# mote_cc3200.net
KiCad netlist of a schematic drawn in EAGLE
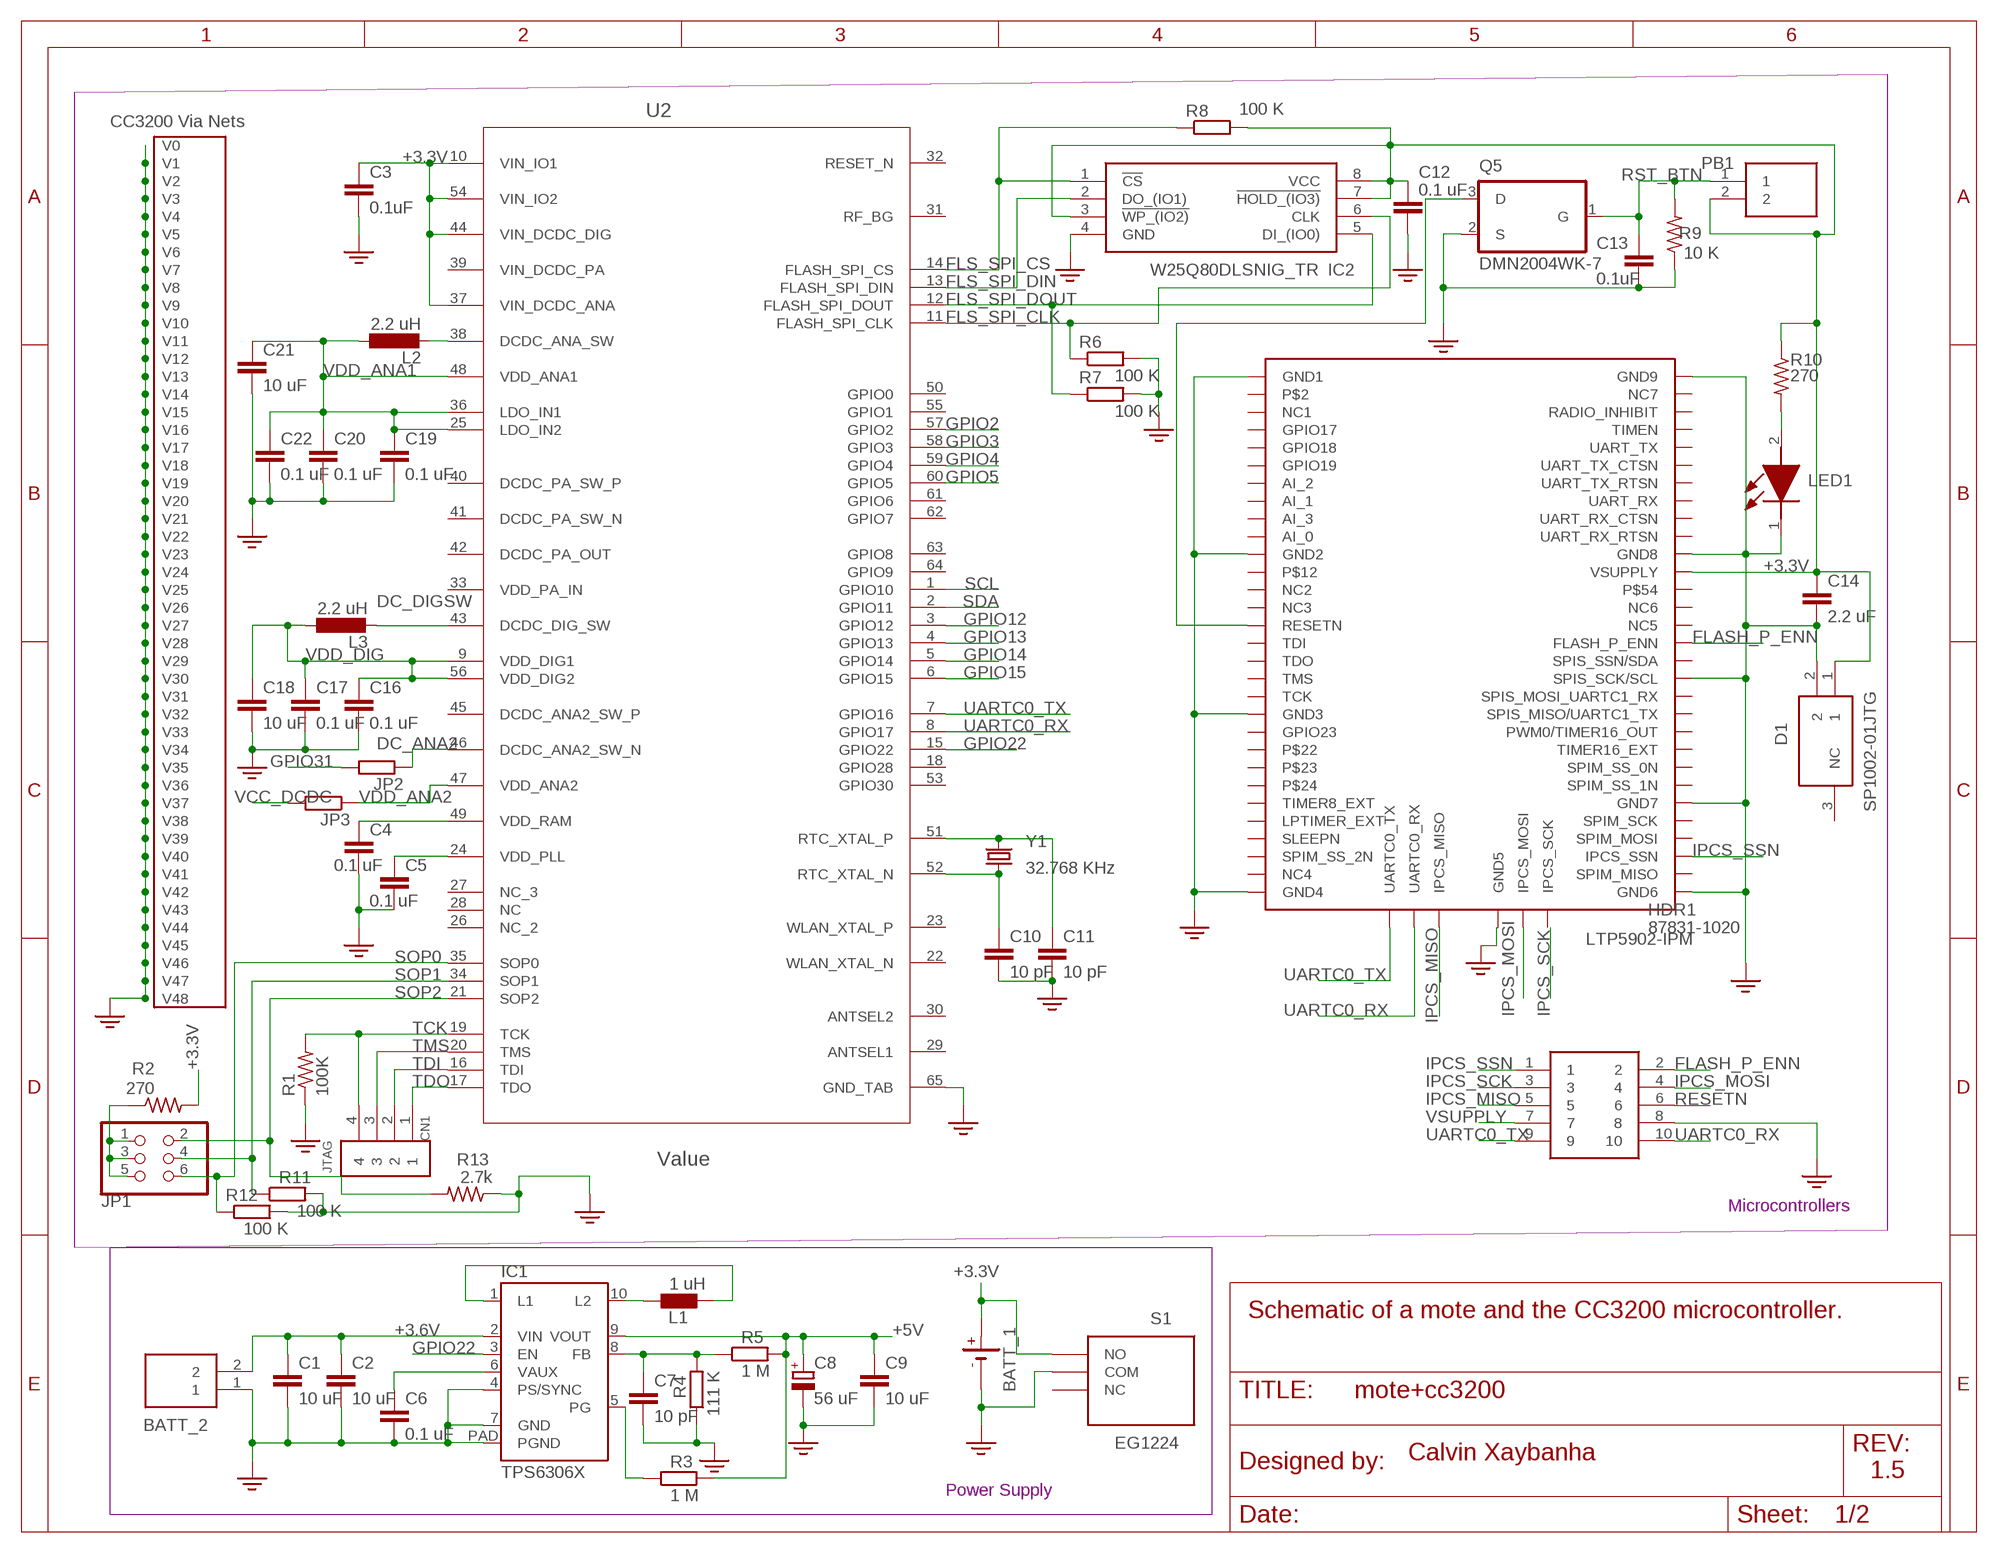
[diagram p0: schematic, sheet 1]
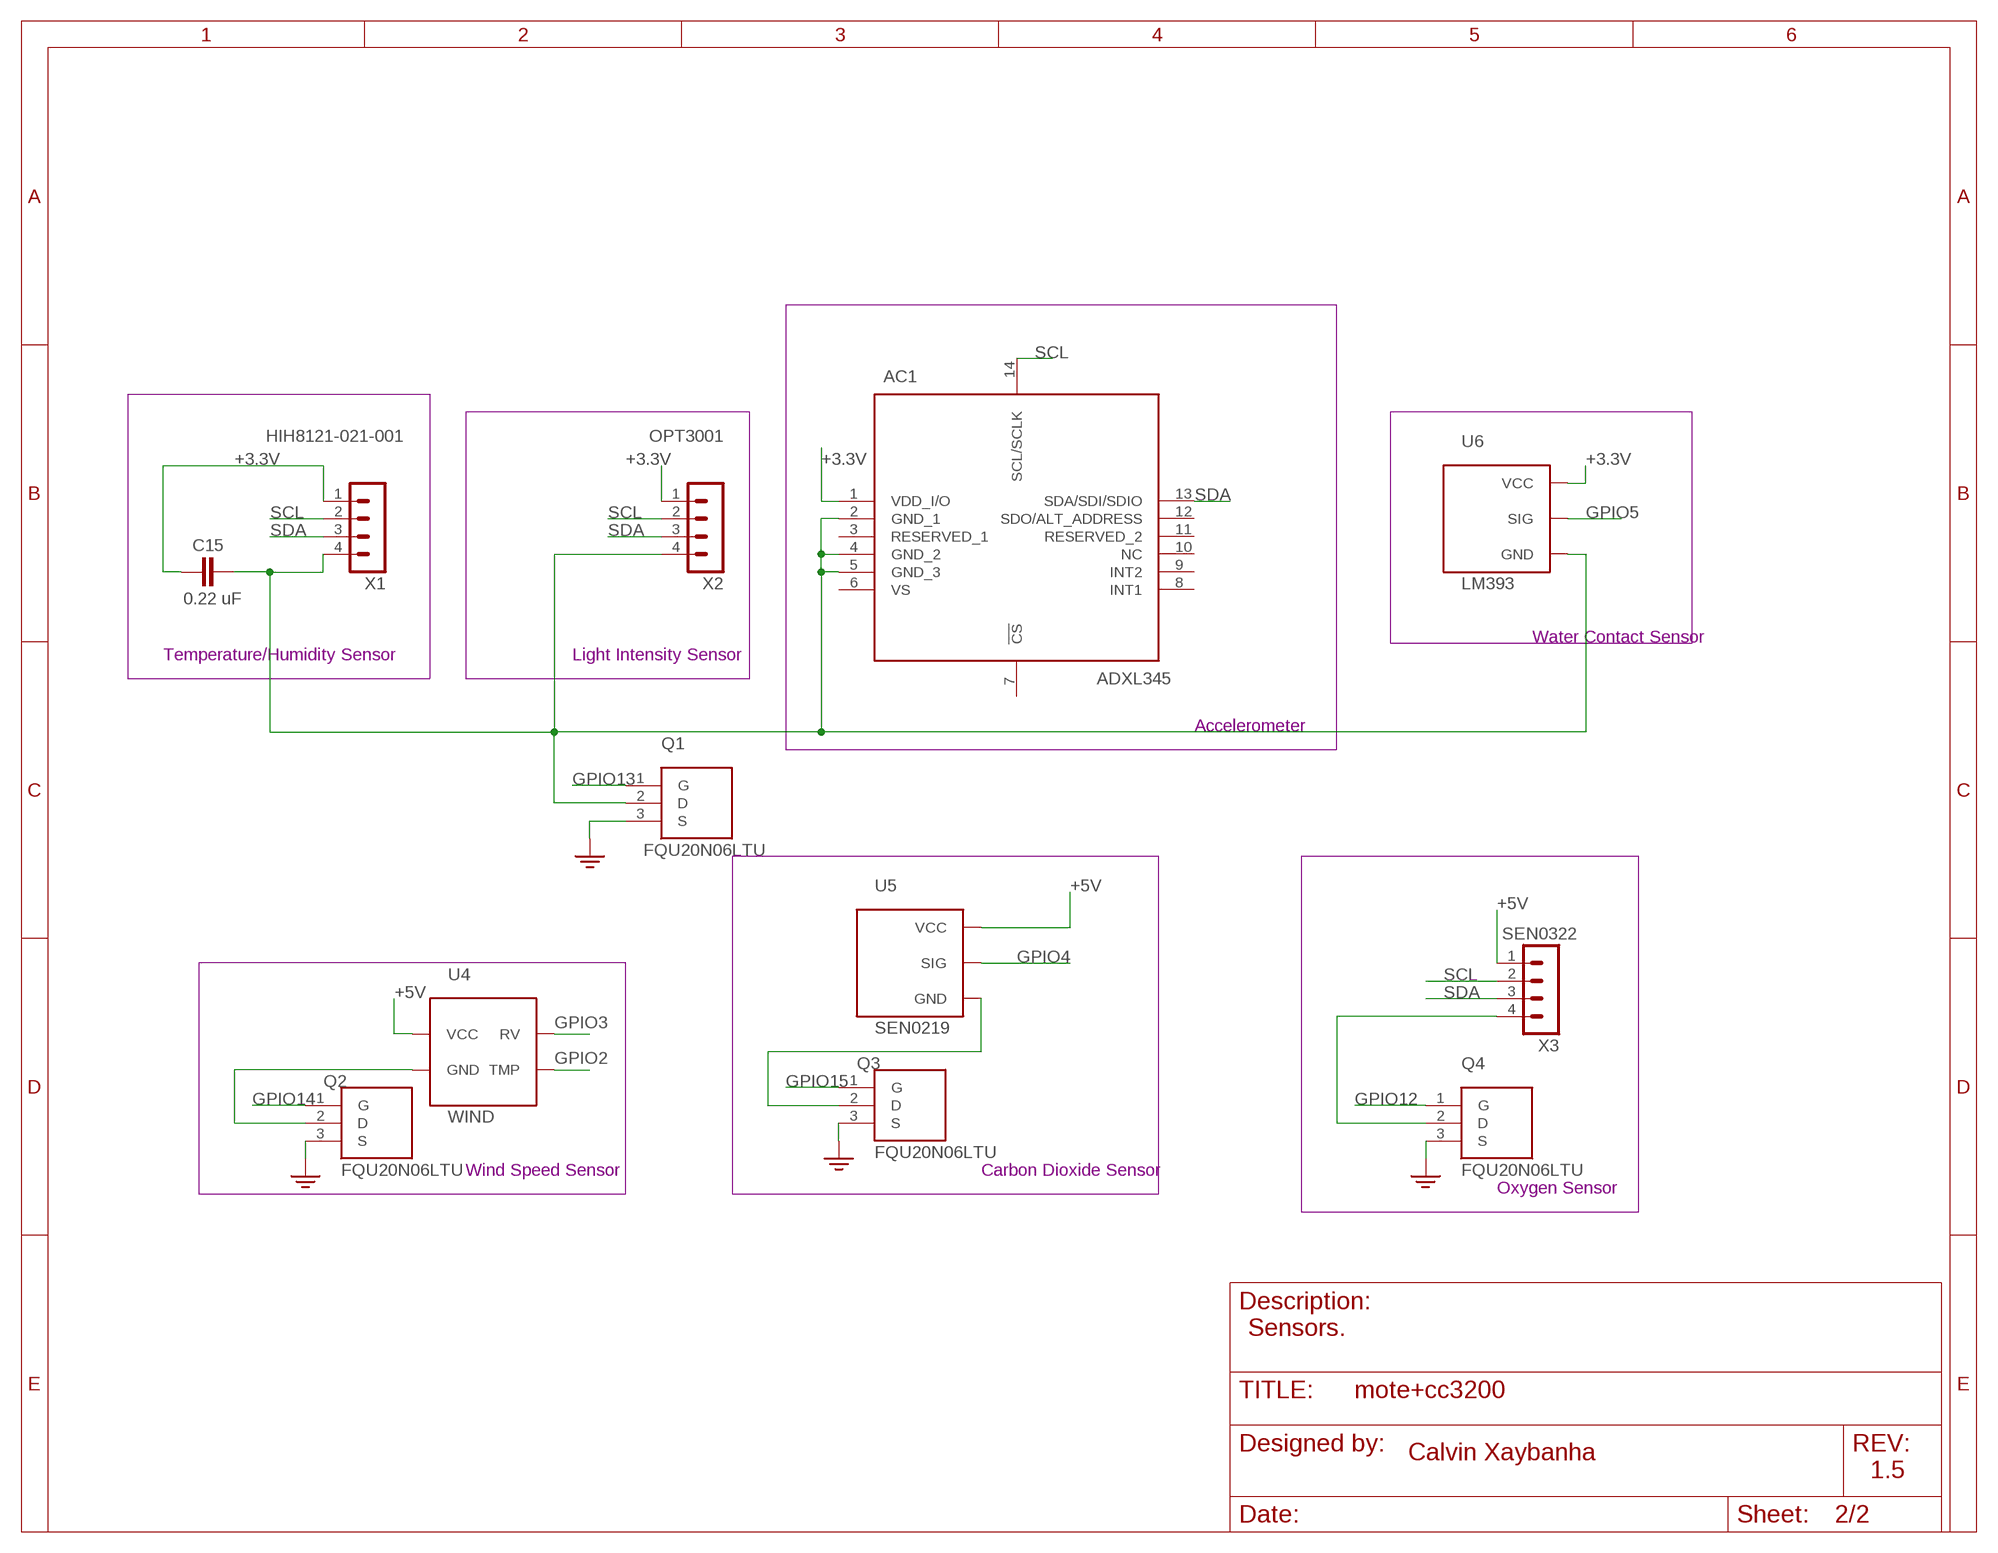
[diagram p1: schematic, sheet 2]

(export (version "E")
  (design (tool "Eeschema 10.0.6"))
  (components
    (comp (ref "BATT_1")
      (value "BATTERY_BR1225/FA")
      (footprint "eagle-import:BATTERY_BR1225_FA")
      (libsource (lib "eagle-import") (part "BATTERY_BR1225/FA"))
    )
    (comp (ref "BATT_2")
      (value "12BH23P-GR")
      (footprint "eagle-import:12BH23PGR")
      (libsource (lib "eagle-import") (part "12BH23P-GR"))
    )
    (comp (ref "C1")
      (value "10 uF")
      (footprint "eagle-import:C1808")
      (libsource (lib "eagle-import") (part "CC1808"))
    )
    (comp (ref "C2")
      (value "10 uF")
      (footprint "eagle-import:C1808")
      (libsource (lib "eagle-import") (part "CC1808"))
    )
    (comp (ref "C3")
      (value "0.1uF")
      (footprint "eagle-import:C5B3.5")
      (libsource (lib "eagle-import") (part "C5/3.5"))
    )
    (comp (ref "C4")
      (value "0.1 uF")
      (footprint "eagle-import:C1808")
      (libsource (lib "eagle-import") (part "C-EUC1808"))
    )
    (comp (ref "C5")
      (value "0.1 uF")
      (footprint "eagle-import:C1808")
      (libsource (lib "eagle-import") (part "C-EUC1808"))
    )
    (comp (ref "C6")
      (value "0.1 uF")
      (footprint "eagle-import:C1808")
      (libsource (lib "eagle-import") (part "C-EUC1808"))
    )
    (comp (ref "C7")
      (value "10 pF")
      (footprint "eagle-import:C1808")
      (libsource (lib "eagle-import") (part "CC1808"))
    )
    (comp (ref "C8")
      (value "56 uF")
      (footprint "eagle-import:E3,5-8")
      (libsource (lib "eagle-import") (part "CPOL-EUE3.5-8"))
    )
    (comp (ref "C9")
      (value "10 uF")
      (footprint "eagle-import:C1808")
      (libsource (lib "eagle-import") (part "CC1808"))
    )
    (comp (ref "C10")
      (value "10 pF")
      (footprint "eagle-import:C1808")
      (libsource (lib "eagle-import") (part "CC1808"))
    )
    (comp (ref "C11")
      (value "10 pF")
      (footprint "eagle-import:C1808")
      (libsource (lib "eagle-import") (part "CC1808"))
    )
    (comp (ref "C12")
      (value "0.1 uF")
      (footprint "eagle-import:C1808")
      (libsource (lib "eagle-import") (part "C-EUC1808"))
    )
    (comp (ref "C13")
      (value "0.1uF")
      (footprint "eagle-import:C5B3.5")
      (libsource (lib "eagle-import") (part "C5/3.5"))
    )
    (comp (ref "C14")
      (value "2.2 uF")
      (footprint "eagle-import:C1808")
      (libsource (lib "eagle-import") (part "CC1808"))
    )
    (comp (ref "C16")
      (value "0.1 uF")
      (footprint "eagle-import:C1808")
      (libsource (lib "eagle-import") (part "C-EUC1808"))
    )
    (comp (ref "C17")
      (value "0.1 uF")
      (footprint "eagle-import:C1808")
      (libsource (lib "eagle-import") (part "C-EUC1808"))
    )
    (comp (ref "C18")
      (value "10 uF")
      (footprint "eagle-import:C1808")
      (libsource (lib "eagle-import") (part "CC1808"))
    )
    (comp (ref "C19")
      (value "0.1 uF")
      (footprint "eagle-import:C1808")
      (libsource (lib "eagle-import") (part "C-EUC1808"))
    )
    (comp (ref "C20")
      (value "0.1 uF")
      (footprint "eagle-import:C1808")
      (libsource (lib "eagle-import") (part "C-EUC1808"))
    )
    (comp (ref "C21")
      (value "10 uF")
      (footprint "eagle-import:C1808")
      (libsource (lib "eagle-import") (part "CC1808"))
    )
    (comp (ref "C22")
      (value "0.1 uF")
      (footprint "eagle-import:C1808")
      (libsource (lib "eagle-import") (part "C-EUC1808"))
    )
    (comp (ref "CN1")
      (value "JTAG")
      (footprint "eagle-import:1X04-BIG")
      (libsource (lib "eagle-import") (part "1X4-BIG"))
    )
    (comp (ref "D1")
      (value "SP1002-01JTG")
      (footprint "eagle-import:SOT132P220X110-3N")
      (fields (field (name "MOUSER_PART_NUMBER") "576-SP1002-01JTG"))
      (libsource (lib "eagle-import") (part "SP1002-01JTG"))
    )
    (comp (ref "HDR1")
      (value "87831-1020")
      (footprint "eagle-import:SHDR10W55P200_2X5_1265X630X640")
      (fields (field (name "MOUSER_PART_NUMBER") "538-87831-1020"))
      (libsource (lib "eagle-import") (part "87831-1020"))
    )
    (comp (ref "IC1")
      (value "TPS6306X")
      (footprint "eagle-import:S-PWSON-N10")
      (libsource (lib "eagle-import") (part "TPS6306X"))
    )
    (comp (ref "IC2")
      (value "W25Q80DLSNIG_TR")
      (footprint "eagle-import:SOIC127P600X175-8N")
      (fields
        (field (name "MANUFACTURER_PART_NUMBER") "W25Q80DLSNIG TR")
        (field (name "MOUSER_PART_NUMBER") "454-W25Q80DLSNIGTR")
      )
      (libsource (lib "eagle-import") (part "W25Q80DLSNIG_TR"))
    )
    (comp (ref "JP1")
      (value "PINHD-2X3/90")
      (footprint "eagle-import:2X03_90")
      (libsource (lib "eagle-import") (part "PINHD-2X3/90"))
    )
    (comp (ref "JP2")
      (value "RR0201")
      (footprint "eagle-import:R0201")
      (libsource (lib "eagle-import") (part "RR0201"))
    )
    (comp (ref "JP3")
      (value "RR0201")
      (footprint "eagle-import:R0201")
      (libsource (lib "eagle-import") (part "RR0201"))
    )
    (comp (ref "L1")
      (value "1 uH")
      (footprint "eagle-import:0204_7")
      (libsource (lib "eagle-import") (part "L0204/7"))
    )
    (comp (ref "L2")
      (value "2.2 uH")
      (footprint "eagle-import:L3216C")
      (libsource (lib "eagle-import") (part "L-EUL3216C"))
    )
    (comp (ref "L3")
      (value "2.2 uH")
      (footprint "eagle-import:L3216C")
      (libsource (lib "eagle-import") (part "L-EUL3216C"))
    )
    (comp (ref "LED1")
      (value "156120RS75000")
      (footprint "eagle-import:LEDM3216X130N")
      (fields (field (name "MOUSER_PART_NUMBER") "710-156120RS75000"))
      (libsource (lib "eagle-import") (part "156120RS75000"))
    )
    (comp (ref "PB1")
      (value "FSMSM")
      (footprint "eagle-import:FSMSM")
      (fields (field (name "MOUSER_PART_NUMBER") "506-FSMSM"))
      (libsource (lib "eagle-import") (part "FSMSM"))
    )
    (comp (ref "Q5")
      (value "DMN2004WK-7")
      (footprint "eagle-import:SC70-3_DCK")
      (libsource (lib "eagle-import") (part "DMN2004WK-7"))
    )
    (comp (ref "R1")
      (value "100K")
      (footprint "eagle-import:0207_10")
      (libsource (lib "eagle-import") (part "R-US_0207/10"))
    )
    (comp (ref "R2")
      (value "270")
      (footprint "eagle-import:RES_1206")
      (fields
        (field (name "DIGIKEY_PART_NUMBER") "WSLP-.05TR-ND")
        (field (name "MANUFACTURER") "Vishay Dale")
        (field (name "MPN") "WSLP1206R0500FEA")
        (field (name "CREATED_BY") "PCBLayout.com")
      )
      (libsource (lib "eagle-import") (part "WSLP1206R0500FEA"))
    )
    (comp (ref "R3")
      (value "1 M")
      (footprint "eagle-import:R5025")
      (libsource (lib "eagle-import") (part "R-EU_R5025"))
    )
    (comp (ref "R4")
      (value "111 K")
      (footprint "eagle-import:R1206")
      (libsource (lib "eagle-import") (part "R-EU_R1206"))
    )
    (comp (ref "R5")
      (value "1 M")
      (footprint "eagle-import:R5025")
      (libsource (lib "eagle-import") (part "R-EU_R5025"))
    )
    (comp (ref "R6")
      (value "100 K")
      (footprint "eagle-import:R1206")
      (libsource (lib "eagle-import") (part "R-EU_R1206"))
    )
    (comp (ref "R7")
      (value "100 K")
      (footprint "eagle-import:R1206")
      (libsource (lib "eagle-import") (part "R-EU_R1206"))
    )
    (comp (ref "R8")
      (value "100 K")
      (footprint "eagle-import:R1206")
      (libsource (lib "eagle-import") (part "R-EU_R1206"))
    )
    (comp (ref "R9")
      (value "10 K")
      (footprint "eagle-import:RES_1206")
      (fields
        (field (name "DIGIKEY_PART_NUMBER") "WSLP-.05TR-ND")
        (field (name "MANUFACTURER") "Vishay Dale")
        (field (name "MPN") "WSLP1206R0500FEA")
        (field (name "CREATED_BY") "PCBLayout.com")
      )
      (libsource (lib "eagle-import") (part "WSLP1206R0500FEA"))
    )
    (comp (ref "R10")
      (value "270")
      (footprint "eagle-import:RES_1206")
      (fields
        (field (name "DIGIKEY_PART_NUMBER") "WSLP-.05TR-ND")
        (field (name "MANUFACTURER") "Vishay Dale")
        (field (name "MPN") "WSLP1206R0500FEA")
        (field (name "CREATED_BY") "PCBLayout.com")
      )
      (libsource (lib "eagle-import") (part "WSLP1206R0500FEA"))
    )
    (comp (ref "R11")
      (value "100 K")
      (footprint "eagle-import:R1206")
      (libsource (lib "eagle-import") (part "R-EU_R1206"))
    )
    (comp (ref "R12")
      (value "100 K")
      (footprint "eagle-import:R1206")
      (libsource (lib "eagle-import") (part "R-EU_R1206"))
    )
    (comp (ref "R13")
      (value "2.7k")
      (footprint "eagle-import:RES_1206")
      (fields
        (field (name "DIGIKEY_PART_NUMBER") "WSLP-.05TR-ND")
        (field (name "MANUFACTURER") "Vishay Dale")
        (field (name "MPN") "WSLP1206R0500FEA")
        (field (name "CREATED_BY") "PCBLayout.com")
      )
      (libsource (lib "eagle-import") (part "WSLP1206R0500FEA"))
    )
    (comp (ref "S1")
      (value "EG1224")
      (footprint "eagle-import:EG1224")
      (fields (field (name "MOUSER_PART_NUMBER") "612-EG1224"))
      (libsource (lib "eagle-import") (part "EG1224"))
    )
    (comp (ref "U2")
      (value "Value")
      (footprint "eagle-import:RGC0064A")
      (fields
        (field (name "ALTERNATEPARTNUMBER") "CC3200R1M2RGC")
        (field (name "MANUFACTURER") "Texas Instruments")
        (field (name "PARTNUMBER") "CC3200R1M2RGCR")
      )
      (libsource (lib "eagle-import") (part "CC3200R1M2RGCR"))
    )
    (comp (ref "U3")
      (value "LTP5902")
      (footprint "eagle-import:LTP5902-MMCX")
      (libsource (lib "eagle-import") (part "LTP5902"))
    )
    (comp (ref "Y1")
      (value "32.768 KHz")
      (footprint "eagle-import:7.0X5.0")
      (libsource (lib "eagle-import") (part "KX-13"))
    )
    (comp (ref "AC1")
      (value "ADXL345")
      (footprint "eagle-import:CC-14-1")
      (libsource (lib "eagle-import") (part "ADXL345"))
    )
    (comp (ref "C15")
      (value "0.22 uF")
      (footprint "eagle-import:C5B3.5")
      (libsource (lib "eagle-import") (part "C5/3.5"))
    )
    (comp (ref "Q1")
      (value "FQU20N06LTU")
      (footprint "eagle-import:TO229P250X658X985-3P")
      (fields (field (name "MOUSER_PART_NUMBER") "512-FQU20N06LTU"))
      (libsource (lib "eagle-import") (part "FQU20N06LTU"))
    )
    (comp (ref "Q2")
      (value "FQU20N06LTU")
      (footprint "eagle-import:TO229P250X658X985-3P")
      (fields (field (name "MOUSER_PART_NUMBER") "512-FQU20N06LTU"))
      (libsource (lib "eagle-import") (part "FQU20N06LTU"))
    )
    (comp (ref "Q3")
      (value "FQU20N06LTU")
      (footprint "eagle-import:TO229P250X658X985-3P")
      (fields (field (name "MOUSER_PART_NUMBER") "512-FQU20N06LTU"))
      (libsource (lib "eagle-import") (part "FQU20N06LTU"))
    )
    (comp (ref "Q4")
      (value "FQU20N06LTU")
      (footprint "eagle-import:TO229P250X658X985-3P")
      (fields (field (name "MOUSER_PART_NUMBER") "512-FQU20N06LTU"))
      (libsource (lib "eagle-import") (part "FQU20N06LTU"))
    )
    (comp (ref "U4")
      (value "WIND")
      (footprint "eagle-import:WIND")
      (libsource (lib "eagle-import") (part "WIND"))
    )
    (comp (ref "U5")
      (value "SEN0219")
      (footprint "eagle-import:SEN0219")
      (libsource (lib "eagle-import") (part "SEN0219"))
    )
    (comp (ref "U6")
      (value "LM393")
      (footprint "eagle-import:LM393")
      (libsource (lib "eagle-import") (part "LM393"))
    )
    (comp (ref "X1")
      (value "HIH8121-021-001")
      (footprint "eagle-import:B4B-PH-K-S")
      (libsource (lib "eagle-import") (part "B4B-PH-K-S"))
    )
    (comp (ref "X2")
      (value "OPT3001")
      (footprint "eagle-import:B4B-PH-K-S")
      (libsource (lib "eagle-import") (part "B4B-PH-K-S"))
    )
    (comp (ref "X3")
      (value "SEN0322")
      (footprint "eagle-import:B4B-PH-K-S")
      (libsource (lib "eagle-import") (part "B4B-PH-K-S"))
    )
  )
  (nets
    (net (code "1") (name "+3.3V") (class "Default")
      (node (ref "AC1") (pin "1") (pinfunction "VDD_I/O_1") (pintype "power_in"))
      (node (ref "BATT_1") (pin "+") (pinfunction "+_+") (pintype "passive"))
      (node (ref "C12") (pin "1") (pinfunction "1_1") (pintype "passive"))
      (node (ref "C14") (pin "1") (pinfunction "1_1") (pintype "passive"))
      (node (ref "C15") (pin "1") (pinfunction "1_1") (pintype "passive"))
      (node (ref "C3") (pin "1") (pinfunction "1_1") (pintype "passive"))
      (node (ref "D1") (pin "1") (pinfunction "1_1") (pintype "bidirectional"))
      (node (ref "IC2") (pin "3") (pinfunction "~{WP_(IO2})_3") (pintype "bidirectional"))
      (node (ref "IC2") (pin "7") (pinfunction "~{HOLD_(IO3})_7") (pintype "bidirectional"))
      (node (ref "IC2") (pin "8") (pinfunction "VCC_8") (pintype "bidirectional"))
      (node (ref "PB1") (pin "2") (pinfunction "2_2") (pintype "bidirectional"))
      (node (ref "R10") (pin "1") (pinfunction "1_1") (pintype "passive"))
      (node (ref "R2") (pin "2") (pinfunction "2_2") (pintype "passive"))
      (node (ref "R8") (pin "2") (pinfunction "2_2") (pintype "passive"))
      (node (ref "S1") (pin "1") (pinfunction "NO_1") (pintype "bidirectional"))
      (node (ref "U2") (pin "10") (pinfunction "VIN_IO1_10") (pintype "power_in"))
      (node (ref "U2") (pin "37") (pinfunction "VIN_DCDC_ANA_37") (pintype "power_in"))
      (node (ref "U2") (pin "44") (pinfunction "VIN_DCDC_DIG_44") (pintype "power_in"))
      (node (ref "U2") (pin "54") (pinfunction "VIN_IO2_54") (pintype "power_in"))
      (node (ref "U3") (pin "P55") (pinfunction "VSUPPLY_P55") (pintype "bidirectional"))
      (node (ref "U6") (pin "P$1") (pinfunction "VCC_P$1") (pintype "power_in"))
      (node (ref "X1") (pin "1") (pinfunction "1_1") (pintype "power_in"))
      (node (ref "X2") (pin "1") (pinfunction "1_1") (pintype "power_in"))
    )
    (net (code "2") (name "+3.6V") (class "Default")
      (node (ref "BATT_2") (pin "2") (pinfunction "2_2") (pintype "bidirectional"))
      (node (ref "C1") (pin "1") (pinfunction "1_1") (pintype "passive"))
      (node (ref "C2") (pin "1") (pinfunction "1_1") (pintype "passive"))
      (node (ref "IC1") (pin "2") (pinfunction "VIN_2") (pintype "passive"))
    )
    (net (code "3") (name "+5V") (class "Default")
      (node (ref "C8") (pin "+") (pinfunction "+_+") (pintype "passive"))
      (node (ref "C9") (pin "1") (pinfunction "1_1") (pintype "passive"))
      (node (ref "IC1") (pin "9") (pinfunction "VOUT_9") (pintype "passive"))
      (node (ref "R3") (pin "2") (pinfunction "2_2") (pintype "passive"))
      (node (ref "R5") (pin "2") (pinfunction "2_2") (pintype "passive"))
      (node (ref "U4") (pin "P$1") (pinfunction "VCC_P$1") (pintype "power_in"))
      (node (ref "U5") (pin "P$1") (pinfunction "VCC_P$1") (pintype "power_in"))
      (node (ref "X3") (pin "1") (pinfunction "1_1") (pintype "power_in"))
    )
    (net (code "4") (name "DCDC_PA_OUT") (class "Default")
      (node (ref "U2") (pin "42") (pinfunction "DCDC_PA_OUT_42") (pintype "power_in"))
    )
    (net (code "5") (name "DCDC_PA_SW_N") (class "Default")
      (node (ref "U2") (pin "41") (pinfunction "DCDC_PA_SW_N_41") (pintype "power_in"))
    )
    (net (code "6") (name "DCDC_PA_SW_P") (class "Default")
      (node (ref "U2") (pin "40") (pinfunction "DCDC_PA_SW_P_40") (pintype "power_in"))
    )
    (net (code "7") (name "DC_ANA2") (class "Default")
      (node (ref "JP2") (pin "1") (pinfunction "1_1") (pintype "passive"))
      (node (ref "U2") (pin "46") (pinfunction "DCDC_ANA2_SW_N_46") (pintype "bidirectional"))
    )
    (net (code "8") (name "DC_DIGSW") (class "Default")
      (node (ref "L3") (pin "2") (pinfunction "2_2") (pintype "passive"))
      (node (ref "U2") (pin "43") (pinfunction "DCDC_DIG_SW_43") (pintype "power_in"))
    )
    (net (code "9") (name "FLASH_P_ENN") (class "Default")
      (node (ref "HDR1") (pin "2") (pinfunction "2_2") (pintype "bidirectional"))
      (node (ref "U3") (pin "P51") (pinfunction "FLASH_P_ENN_P51") (pintype "bidirectional"))
    )
    (net (code "10") (name "FLS_SPI_CLK") (class "Default")
      (node (ref "IC2") (pin "6") (pinfunction "CLK_6") (pintype "bidirectional"))
      (node (ref "R6") (pin "1") (pinfunction "1_1") (pintype "passive"))
      (node (ref "U2") (pin "11") (pinfunction "FLASH_SPI_CLK_11") (pintype "output"))
    )
    (net (code "11") (name "FLS_SPI_CS") (class "Default")
      (node (ref "IC2") (pin "1") (pinfunction "~{CS}_1") (pintype "bidirectional"))
      (node (ref "R8") (pin "1") (pinfunction "1_1") (pintype "passive"))
      (node (ref "U2") (pin "14") (pinfunction "FLASH_SPI_CS_14") (pintype "output"))
    )
    (net (code "12") (name "FLS_SPI_DIN") (class "Default")
      (node (ref "IC2") (pin "2") (pinfunction "DO_(IO1)_2") (pintype "bidirectional"))
      (node (ref "U2") (pin "13") (pinfunction "FLASH_SPI_DIN_13") (pintype "input"))
    )
    (net (code "13") (name "FLS_SPI_DOUT") (class "Default")
      (node (ref "IC2") (pin "5") (pinfunction "DI_(IO0)_5") (pintype "bidirectional"))
      (node (ref "R7") (pin "1") (pinfunction "1_1") (pintype "passive"))
      (node (ref "U2") (pin "12") (pinfunction "FLASH_SPI_DOUT_12") (pintype "output"))
    )
    (net (code "14") (name "GND") (class "Default")
      (node (ref "BATT_1") (pin "-") (pinfunction "-_-") (pintype "passive"))
      (node (ref "BATT_2") (pin "1") (pinfunction "1_1") (pintype "bidirectional"))
      (node (ref "C1") (pin "2") (pinfunction "2_2") (pintype "passive"))
      (node (ref "C10") (pin "2") (pinfunction "2_2") (pintype "passive"))
      (node (ref "C11") (pin "2") (pinfunction "2_2") (pintype "passive"))
      (node (ref "C12") (pin "2") (pinfunction "2_2") (pintype "passive"))
      (node (ref "C13") (pin "1") (pinfunction "1_1") (pintype "passive"))
      (node (ref "C14") (pin "2") (pinfunction "2_2") (pintype "passive"))
      (node (ref "C16") (pin "2") (pinfunction "2_2") (pintype "passive"))
      (node (ref "C17") (pin "2") (pinfunction "2_2") (pintype "passive"))
      (node (ref "C18") (pin "2") (pinfunction "2_2") (pintype "passive"))
      (node (ref "C19") (pin "2") (pinfunction "2_2") (pintype "passive"))
      (node (ref "C2") (pin "2") (pinfunction "2_2") (pintype "passive"))
      (node (ref "C20") (pin "2") (pinfunction "2_2") (pintype "passive"))
      (node (ref "C21") (pin "2") (pinfunction "2_2") (pintype "passive"))
      (node (ref "C22") (pin "2") (pinfunction "2_2") (pintype "passive"))
      (node (ref "C3") (pin "2") (pinfunction "2_2") (pintype "passive"))
      (node (ref "C4") (pin "2") (pinfunction "2_2") (pintype "passive"))
      (node (ref "C5") (pin "2") (pinfunction "2_2") (pintype "passive"))
      (node (ref "C6") (pin "2") (pinfunction "2_2") (pintype "passive"))
      (node (ref "C7") (pin "2") (pinfunction "2_2") (pintype "passive"))
      (node (ref "C8") (pin "-") (pinfunction "-_-") (pintype "passive"))
      (node (ref "C9") (pin "2") (pinfunction "2_2") (pintype "passive"))
      (node (ref "D1") (pin "2") (pinfunction "2_2") (pintype "bidirectional"))
      (node (ref "HDR1") (pin "8") (pinfunction "8_8") (pintype "bidirectional"))
      (node (ref "IC1") (pin "4") (pinfunction "PS/SYNC_4") (pintype "passive"))
      (node (ref "IC1") (pin "7") (pinfunction "GND_7") (pintype "passive"))
      (node (ref "IC1") (pin "PAD") (pinfunction "PGND_PAD") (pintype "passive"))
      (node (ref "IC2") (pin "4") (pinfunction "GND_4") (pintype "bidirectional"))
      (node (ref "LED1") (pin "1") (pinfunction "K_1") (pintype "bidirectional"))
      (node (ref "Q1") (pin "3") (pinfunction "S_3") (pintype "bidirectional"))
      (node (ref "Q2") (pin "3") (pinfunction "S_3") (pintype "bidirectional"))
      (node (ref "Q3") (pin "3") (pinfunction "S_3") (pintype "bidirectional"))
      (node (ref "Q4") (pin "3") (pinfunction "S_3") (pintype "bidirectional"))
      (node (ref "Q5") (pin "2") (pinfunction "S_2") (pintype "bidirectional"))
      (node (ref "R1") (pin "1") (pinfunction "1_1") (pintype "passive"))
      (node (ref "R11") (pin "2") (pinfunction "2_2") (pintype "passive"))
      (node (ref "R12") (pin "2") (pinfunction "2_2") (pintype "passive"))
      (node (ref "R13") (pin "1") (pinfunction "1_1") (pintype "passive"))
      (node (ref "R4") (pin "1") (pinfunction "1_1") (pintype "passive"))
      (node (ref "R6") (pin "2") (pinfunction "2_2") (pintype "passive"))
      (node (ref "R7") (pin "2") (pinfunction "2_2") (pintype "passive"))
      (node (ref "R9") (pin "1") (pinfunction "1_1") (pintype "passive"))
      (node (ref "S1") (pin "2") (pinfunction "COM_2") (pintype "bidirectional"))
      (node (ref "U2") (pin "65") (pinfunction "GND_TAB_65") (pintype "power_in"))
      (node (ref "U2") (pin "V") (pinfunction "V0_V") (pintype "bidirectional"))
      (node (ref "U2") (pin "V_1") (pinfunction "V1_V_1") (pintype "bidirectional"))
      (node (ref "U2") (pin "V_10") (pinfunction "V10_V_10") (pintype "bidirectional"))
      (node (ref "U2") (pin "V_11") (pinfunction "V11_V_11") (pintype "bidirectional"))
      (node (ref "U2") (pin "V_12") (pinfunction "V12_V_12") (pintype "bidirectional"))
      (node (ref "U2") (pin "V_13") (pinfunction "V13_V_13") (pintype "bidirectional"))
      (node (ref "U2") (pin "V_14") (pinfunction "V14_V_14") (pintype "bidirectional"))
      (node (ref "U2") (pin "V_15") (pinfunction "V15_V_15") (pintype "bidirectional"))
      (node (ref "U2") (pin "V_16") (pinfunction "V16_V_16") (pintype "bidirectional"))
      (node (ref "U2") (pin "V_17") (pinfunction "V17_V_17") (pintype "bidirectional"))
      (node (ref "U2") (pin "V_18") (pinfunction "V18_V_18") (pintype "bidirectional"))
      (node (ref "U2") (pin "V_19") (pinfunction "V19_V_19") (pintype "bidirectional"))
      (node (ref "U2") (pin "V_2") (pinfunction "V2_V_2") (pintype "bidirectional"))
      (node (ref "U2") (pin "V_20") (pinfunction "V20_V_20") (pintype "bidirectional"))
      (node (ref "U2") (pin "V_21") (pinfunction "V21_V_21") (pintype "bidirectional"))
      (node (ref "U2") (pin "V_22") (pinfunction "V22_V_22") (pintype "bidirectional"))
      (node (ref "U2") (pin "V_23") (pinfunction "V23_V_23") (pintype "bidirectional"))
      (node (ref "U2") (pin "V_24") (pinfunction "V24_V_24") (pintype "bidirectional"))
      (node (ref "U2") (pin "V_25") (pinfunction "V25_V_25") (pintype "bidirectional"))
      (node (ref "U2") (pin "V_26") (pinfunction "V26_V_26") (pintype "bidirectional"))
      (node (ref "U2") (pin "V_27") (pinfunction "V27_V_27") (pintype "bidirectional"))
      (node (ref "U2") (pin "V_28") (pinfunction "V28_V_28") (pintype "bidirectional"))
      (node (ref "U2") (pin "V_29") (pinfunction "V29_V_29") (pintype "bidirectional"))
      (node (ref "U2") (pin "V_3") (pinfunction "V3_V_3") (pintype "bidirectional"))
      (node (ref "U2") (pin "V_30") (pinfunction "V30_V_30") (pintype "bidirectional"))
      (node (ref "U2") (pin "V_31") (pinfunction "V31_V_31") (pintype "bidirectional"))
      (node (ref "U2") (pin "V_32") (pinfunction "V32_V_32") (pintype "bidirectional"))
      (node (ref "U2") (pin "V_33") (pinfunction "V33_V_33") (pintype "bidirectional"))
      (node (ref "U2") (pin "V_34") (pinfunction "V34_V_34") (pintype "bidirectional"))
      (node (ref "U2") (pin "V_35") (pinfunction "V35_V_35") (pintype "bidirectional"))
      (node (ref "U2") (pin "V_36") (pinfunction "V36_V_36") (pintype "bidirectional"))
      (node (ref "U2") (pin "V_37") (pinfunction "V37_V_37") (pintype "bidirectional"))
      (node (ref "U2") (pin "V_38") (pinfunction "V38_V_38") (pintype "bidirectional"))
      (node (ref "U2") (pin "V_39") (pinfunction "V39_V_39") (pintype "bidirectional"))
      (node (ref "U2") (pin "V_4") (pinfunction "V4_V_4") (pintype "bidirectional"))
      (node (ref "U2") (pin "V_40") (pinfunction "V40_V_40") (pintype "bidirectional"))
      (node (ref "U2") (pin "V_41") (pinfunction "V41_V_41") (pintype "bidirectional"))
      (node (ref "U2") (pin "V_42") (pinfunction "V42_V_42") (pintype "bidirectional"))
      (node (ref "U2") (pin "V_43") (pinfunction "V43_V_43") (pintype "bidirectional"))
      (node (ref "U2") (pin "V_44") (pinfunction "V44_V_44") (pintype "bidirectional"))
      (node (ref "U2") (pin "V_45") (pinfunction "V45_V_45") (pintype "bidirectional"))
      (node (ref "U2") (pin "V_46") (pinfunction "V46_V_46") (pintype "bidirectional"))
      (node (ref "U2") (pin "V_47") (pinfunction "V47_V_47") (pintype "bidirectional"))
      (node (ref "U2") (pin "V_48") (pinfunction "V48_V_48") (pintype "bidirectional"))
      (node (ref "U2") (pin "V_5") (pinfunction "V5_V_5") (pintype "bidirectional"))
      (node (ref "U2") (pin "V_6") (pinfunction "V6_V_6") (pintype "bidirectional"))
      (node (ref "U2") (pin "V_7") (pinfunction "V7_V_7") (pintype "bidirectional"))
      (node (ref "U2") (pin "V_8") (pinfunction "V8_V_8") (pintype "bidirectional"))
      (node (ref "U2") (pin "V_9") (pinfunction "V9_V_9") (pintype "bidirectional"))
      (node (ref "U3") (pin "P1") (pinfunction "GND1_P1") (pintype "bidirectional"))
      (node (ref "U3") (pin "P11") (pinfunction "GND2_P11") (pintype "bidirectional"))
      (node (ref "U3") (pin "P20") (pinfunction "GND3_P20") (pintype "bidirectional"))
      (node (ref "U3") (pin "P30") (pinfunction "GND4_P30") (pintype "bidirectional"))
      (node (ref "U3") (pin "P34") (pinfunction "GND5_P34") (pintype "bidirectional"))
      (node (ref "U3") (pin "P37") (pinfunction "GND6_P37") (pintype "bidirectional"))
      (node (ref "U3") (pin "P42") (pinfunction "GND7_P42") (pintype "bidirectional"))
      (node (ref "U3") (pin "P49") (pinfunction "SPIS_SCK/SCL_P49") (pintype "bidirectional"))
      (node (ref "U3") (pin "P56") (pinfunction "GND8_P56") (pintype "bidirectional"))
      (node (ref "U3") (pin "P66") (pinfunction "GND9_P66") (pintype "bidirectional"))
    )
    (net (code "15") (name "GPIO2") (class "Default")
      (node (ref "U2") (pin "57") (pinfunction "GPIO2_57") (pintype "bidirectional"))
      (node (ref "U4") (pin "P$4") (pinfunction "TMP_P$4") (pintype "bidirectional"))
    )
    (net (code "16") (name "GPIO3") (class "Default")
      (node (ref "U2") (pin "58") (pinfunction "GPIO3_58") (pintype "bidirectional"))
      (node (ref "U4") (pin "P$3") (pinfunction "RV_P$3") (pintype "bidirectional"))
    )
    (net (code "17") (name "GPIO4") (class "Default")
      (node (ref "U2") (pin "59") (pinfunction "GPIO4_59") (pintype "bidirectional"))
      (node (ref "U5") (pin "P$2") (pinfunction "SIG_P$2") (pintype "bidirectional"))
    )
    (net (code "18") (name "GPIO5") (class "Default")
      (node (ref "U2") (pin "60") (pinfunction "GPIO5_60") (pintype "bidirectional"))
      (node (ref "U6") (pin "P$2") (pinfunction "SIG_P$2") (pintype "bidirectional"))
    )
    (net (code "19") (name "GPIO12") (class "Default")
      (node (ref "Q4") (pin "1") (pinfunction "G_1") (pintype "bidirectional"))
      (node (ref "U2") (pin "3") (pinfunction "GPIO12_3") (pintype "bidirectional"))
    )
    (net (code "20") (name "GPIO13") (class "Default")
      (node (ref "Q1") (pin "1") (pinfunction "G_1") (pintype "bidirectional"))
      (node (ref "U2") (pin "4") (pinfunction "GPIO13_4") (pintype "bidirectional"))
    )
    (net (code "21") (name "GPIO14") (class "Default")
      (node (ref "Q2") (pin "1") (pinfunction "G_1") (pintype "bidirectional"))
      (node (ref "U2") (pin "5") (pinfunction "GPIO14_5") (pintype "bidirectional"))
    )
    (net (code "22") (name "GPIO15") (class "Default")
      (node (ref "Q3") (pin "1") (pinfunction "G_1") (pintype "bidirectional"))
      (node (ref "U2") (pin "6") (pinfunction "GPIO15_6") (pintype "bidirectional"))
    )
    (net (code "23") (name "GPIO22") (class "Default")
      (node (ref "IC1") (pin "3") (pinfunction "EN_3") (pintype "passive"))
      (node (ref "U2") (pin "15") (pinfunction "GPIO22_15") (pintype "bidirectional"))
    )
    (net (code "24") (name "GPIO31") (class "Default")
      (node (ref "JP2") (pin "2") (pinfunction "2_2") (pintype "passive"))
    )
    (net (code "25") (name "IPCS_MISO") (class "Default")
      (node (ref "HDR1") (pin "5") (pinfunction "5_5") (pintype "bidirectional"))
      (node (ref "U3") (pin "P33") (pinfunction "IPCS_MISO_P33") (pintype "bidirectional"))
    )
    (net (code "26") (name "IPCS_MOSI") (class "Default")
      (node (ref "U3") (pin "P35") (pinfunction "IPCS_MOSI_P35") (pintype "bidirectional"))
    )
    (net (code "27") (name "IPCS_SCK") (class "Default")
      (node (ref "HDR1") (pin "3") (pinfunction "3_3") (pintype "bidirectional"))
    )
    (net (code "28") (name "IPCS_SSN") (class "Default")
      (node (ref "HDR1") (pin "1") (pinfunction "1_1") (pintype "bidirectional"))
      (node (ref "U3") (pin "P39") (pinfunction "IPCS_SSN_P39") (pintype "bidirectional"))
    )
    (net (code "29") (name "Net-(AC1-GND_1)") (class "Default")
      (node (ref "AC1") (pin "2") (pinfunction "GND_1_2") (pintype "power_in"))
      (node (ref "AC1") (pin "4") (pinfunction "GND_2_4") (pintype "power_in"))
      (node (ref "AC1") (pin "5") (pinfunction "GND_3_5") (pintype "power_in"))
      (node (ref "C15") (pin "2") (pinfunction "2_2") (pintype "passive"))
      (node (ref "Q1") (pin "2") (pinfunction "D_2") (pintype "bidirectional"))
      (node (ref "U6") (pin "P$3") (pinfunction "GND_P$3") (pintype "power_in"))
      (node (ref "X1") (pin "4") (pinfunction "4_4") (pintype "bidirectional"))
      (node (ref "X2") (pin "4") (pinfunction "4_4") (pintype "bidirectional"))
    )
    (net (code "30") (name "Net-(IC1-FB)") (class "Default")
      (node (ref "C7") (pin "1") (pinfunction "1_1") (pintype "passive"))
      (node (ref "IC1") (pin "8") (pinfunction "FB_8") (pintype "passive"))
      (node (ref "R4") (pin "2") (pinfunction "2_2") (pintype "passive"))
      (node (ref "R5") (pin "1") (pinfunction "1_1") (pintype "passive"))
    )
    (net (code "31") (name "Net-(IC1-L1)") (class "Default")
      (node (ref "IC1") (pin "1") (pinfunction "L1_1") (pintype "passive"))
      (node (ref "L1") (pin "2") (pinfunction "2_2") (pintype "passive"))
    )
    (net (code "32") (name "Net-(IC1-L2)") (class "Default")
      (node (ref "IC1") (pin "10") (pinfunction "L2_10") (pintype "passive"))
      (node (ref "L1") (pin "1") (pinfunction "1_1") (pintype "passive"))
    )
    (net (code "33") (name "Net-(IC1-PG)") (class "Default")
      (node (ref "IC1") (pin "5") (pinfunction "PG_5") (pintype "passive"))
      (node (ref "R3") (pin "1") (pinfunction "1_1") (pintype "passive"))
    )
    (net (code "34") (name "Net-(IC1-VAUX)") (class "Default")
      (node (ref "C6") (pin "1") (pinfunction "1_1") (pintype "passive"))
      (node (ref "IC1") (pin "6") (pinfunction "VAUX_6") (pintype "passive"))
    )
    (net (code "35") (name "Net-(JP1-Pad1)") (class "Default")
      (node (ref "JP1") (pin "1") (pinfunction "1_1") (pintype "passive"))
      (node (ref "JP1") (pin "3") (pinfunction "3_3") (pintype "passive"))
      (node (ref "JP1") (pin "5") (pinfunction "5_5") (pintype "passive"))
      (node (ref "R2") (pin "1") (pinfunction "1_1") (pintype "passive"))
    )
    (net (code "36") (name "Net-(LED1-A)") (class "Default")
      (node (ref "LED1") (pin "2") (pinfunction "A_2") (pintype "bidirectional"))
      (node (ref "R10") (pin "2") (pinfunction "2_2") (pintype "passive"))
    )
    (net (code "37") (name "Net-(Q2-D)") (class "Default")
      (node (ref "Q2") (pin "2") (pinfunction "D_2") (pintype "bidirectional"))
      (node (ref "U4") (pin "P$2") (pinfunction "GND_P$2") (pintype "power_in"))
    )
    (net (code "38") (name "Net-(Q3-D)") (class "Default")
      (node (ref "Q3") (pin "2") (pinfunction "D_2") (pintype "bidirectional"))
      (node (ref "U5") (pin "P$3") (pinfunction "GND_P$3") (pintype "power_in"))
    )
    (net (code "39") (name "Net-(Q4-D)") (class "Default")
      (node (ref "Q4") (pin "2") (pinfunction "D_2") (pintype "bidirectional"))
      (node (ref "X3") (pin "4") (pinfunction "4_4") (pintype "bidirectional"))
    )
    (net (code "40") (name "Net-(U2-DCDC_ANA_SW)") (class "Default")
      (node (ref "L2") (pin "2") (pinfunction "2_2") (pintype "passive"))
      (node (ref "U2") (pin "38") (pinfunction "DCDC_ANA_SW_38") (pintype "power_in"))
    )
    (net (code "41") (name "Net-(U2-RTC_XTAL_N)") (class "Default")
      (node (ref "C10") (pin "1") (pinfunction "1_1") (pintype "passive"))
      (node (ref "U2") (pin "52") (pinfunction "RTC_XTAL_N_52") (pintype "passive"))
      (node (ref "Y1") (pin "1") (pinfunction "1_1") (pintype "passive"))
    )
    (net (code "42") (name "Net-(U2-RTC_XTAL_P)") (class "Default")
      (node (ref "C11") (pin "1") (pinfunction "1_1") (pintype "passive"))
      (node (ref "U2") (pin "51") (pinfunction "RTC_XTAL_P_51") (pintype "passive"))
      (node (ref "Y1") (pin "3") (pinfunction "2_3") (pintype "passive"))
    )
    (net (code "43") (name "Net-(U2-VDD_PLL)") (class "Default")
      (node (ref "C5") (pin "1") (pinfunction "1_1") (pintype "passive"))
      (node (ref "U2") (pin "24") (pinfunction "VDD_PLL_24") (pintype "power_in"))
    )
    (net (code "44") (name "Net-(U2-VDD_RAM)") (class "Default")
      (node (ref "C4") (pin "1") (pinfunction "1_1") (pintype "passive"))
      (node (ref "U2") (pin "49") (pinfunction "VDD_RAM_49") (pintype "power_in"))
    )
    (net (code "45") (name "RESETN") (class "Default")
      (node (ref "HDR1") (pin "6") (pinfunction "6_6") (pintype "bidirectional"))
      (node (ref "Q5") (pin "3") (pinfunction "D_3") (pintype "bidirectional"))
      (node (ref "U3") (pin "P15") (pinfunction "RESETN_P15") (pintype "bidirectional"))
    )
    (net (code "46") (name "RST_BTN") (class "Default")
      (node (ref "C13") (pin "2") (pinfunction "2_2") (pintype "passive"))
      (node (ref "PB1") (pin "1") (pinfunction "1_1") (pintype "bidirectional"))
      (node (ref "Q5") (pin "1") (pinfunction "G_1") (pintype "bidirectional"))
      (node (ref "R9") (pin "2") (pinfunction "2_2") (pintype "passive"))
    )
    (net (code "47") (name "SCL") (class "Default")
      (node (ref "AC1") (pin "14") (pinfunction "SCL/SCLK_14") (pintype "input"))
      (node (ref "U2") (pin "1") (pinfunction "GPIO10_1") (pintype "bidirectional"))
      (node (ref "X1") (pin "2") (pinfunction "2_2") (pintype "power_in"))
      (node (ref "X2") (pin "2") (pinfunction "2_2") (pintype "power_in"))
      (node (ref "X3") (pin "2") (pinfunction "2_2") (pintype "power_in"))
    )
    (net (code "48") (name "SDA") (class "Default")
      (node (ref "AC1") (pin "13") (pinfunction "SDA/SDI/SDIO_13") (pintype "bidirectional"))
      (node (ref "U2") (pin "2") (pinfunction "GPIO11_2") (pintype "bidirectional"))
      (node (ref "X1") (pin "3") (pinfunction "3_3") (pintype "bidirectional"))
      (node (ref "X2") (pin "3") (pinfunction "3_3") (pintype "bidirectional"))
      (node (ref "X3") (pin "3") (pinfunction "3_3") (pintype "bidirectional"))
    )
    (net (code "49") (name "SOP0") (class "Default")
      (node (ref "JP1") (pin "6") (pinfunction "6_6") (pintype "passive"))
      (node (ref "R12") (pin "1") (pinfunction "1_1") (pintype "passive"))
      (node (ref "U2") (pin "35") (pinfunction "SOP0_35") (pintype "input"))
    )
    (net (code "50") (name "SOP1") (class "Default")
      (node (ref "JP1") (pin "4") (pinfunction "4_4") (pintype "passive"))
      (node (ref "R11") (pin "1") (pinfunction "1_1") (pintype "passive"))
      (node (ref "U2") (pin "34") (pinfunction "SOP1_34") (pintype "input"))
    )
    (net (code "51") (name "SOP2") (class "Default")
      (node (ref "JP1") (pin "2") (pinfunction "2_2") (pintype "passive"))
      (node (ref "R13") (pin "2") (pinfunction "2_2") (pintype "passive"))
      (node (ref "U2") (pin "21") (pinfunction "SOP2_21") (pintype "output"))
    )
    (net (code "52") (name "TCK") (class "Default")
      (node (ref "CN1") (pin "4") (pinfunction "4_4") (pintype "bidirectional"))
      (node (ref "R1") (pin "2") (pinfunction "2_2") (pintype "passive"))
      (node (ref "U2") (pin "19") (pinfunction "TCK_19") (pintype "bidirectional"))
    )
    (net (code "53") (name "TDI") (class "Default")
      (node (ref "CN1") (pin "2") (pinfunction "2_2") (pintype "bidirectional"))
      (node (ref "U2") (pin "16") (pinfunction "TDI_16") (pintype "bidirectional"))
    )
    (net (code "54") (name "TDO") (class "Default")
      (node (ref "CN1") (pin "1") (pinfunction "1_1") (pintype "bidirectional"))
      (node (ref "U2") (pin "17") (pinfunction "TDO_17") (pintype "bidirectional"))
    )
    (net (code "55") (name "TMS") (class "Default")
      (node (ref "CN1") (pin "3") (pinfunction "3_3") (pintype "bidirectional"))
      (node (ref "U2") (pin "20") (pinfunction "TMS_20") (pintype "bidirectional"))
    )
    (net (code "56") (name "UARTC0_RX") (class "Default")
      (node (ref "HDR1") (pin "10") (pinfunction "10_10") (pintype "bidirectional"))
      (node (ref "U2") (pin "8") (pinfunction "GPIO17_8") (pintype "bidirectional"))
      (node (ref "U3") (pin "P32") (pinfunction "UARTC0_RX_P32") (pintype "bidirectional"))
    )
    (net (code "57") (name "UARTC0_TX") (class "Default")
      (node (ref "HDR1") (pin "9") (pinfunction "9_9") (pintype "bidirectional"))
      (node (ref "U2") (pin "7") (pinfunction "GPIO16_7") (pintype "bidirectional"))
      (node (ref "U3") (pin "P31") (pinfunction "UARTC0_TX_P31") (pintype "bidirectional"))
    )
    (net (code "58") (name "VCC_DCDC") (class "Default")
      (node (ref "JP3") (pin "2") (pinfunction "2_2") (pintype "passive"))
    )
    (net (code "59") (name "VDD_ANA1") (class "Default")
      (node (ref "C19") (pin "1") (pinfunction "1_1") (pintype "passive"))
      (node (ref "C20") (pin "1") (pinfunction "1_1") (pintype "passive"))
      (node (ref "C21") (pin "1") (pinfunction "1_1") (pintype "passive"))
      (node (ref "C22") (pin "1") (pinfunction "1_1") (pintype "passive"))
      (node (ref "L2") (pin "1") (pinfunction "1_1") (pintype "passive"))
      (node (ref "U2") (pin "25") (pinfunction "LDO_IN2_25") (pintype "power_in"))
      (node (ref "U2") (pin "36") (pinfunction "LDO_IN1_36") (pintype "power_in"))
      (node (ref "U2") (pin "48") (pinfunction "VDD_ANA1_48") (pintype "power_in"))
    )
    (net (code "60") (name "VDD_ANA2") (class "Default")
      (node (ref "JP3") (pin "1") (pinfunction "1_1") (pintype "passive"))
      (node (ref "U2") (pin "47") (pinfunction "VDD_ANA2_47") (pintype "power_in"))
    )
    (net (code "61") (name "VDD_DIG") (class "Default")
      (node (ref "C16") (pin "1") (pinfunction "1_1") (pintype "passive"))
      (node (ref "C17") (pin "1") (pinfunction "1_1") (pintype "passive"))
      (node (ref "C18") (pin "1") (pinfunction "1_1") (pintype "passive"))
      (node (ref "L3") (pin "1") (pinfunction "1_1") (pintype "passive"))
      (node (ref "U2") (pin "56") (pinfunction "VDD_DIG2_56") (pintype "power_in"))
      (node (ref "U2") (pin "9") (pinfunction "VDD_DIG1_9") (pintype "power_in"))
    )
    (net (code "62") (name "VDD_PA_IN") (class "Default")
      (node (ref "U2") (pin "33") (pinfunction "VDD_PA_IN_33") (pintype "power_in"))
    )
    (net (code "63") (name "VIN_DCDC_PA") (class "Default")
      (node (ref "U2") (pin "39") (pinfunction "VIN_DCDC_PA_39") (pintype "power_in"))
    )
    (net (code "64") (name "VSUPPLY") (class "Default")
      (node (ref "HDR1") (pin "7") (pinfunction "7_7") (pintype "bidirectional"))
    )
    (net (code "65") (name "unconnected-(AC1-INT1-Pad8)") (class "Default")
      (node (ref "AC1") (pin "8") (pinfunction "INT1_8") (pintype "input"))
    )
    (net (code "66") (name "unconnected-(AC1-INT2-Pad9)") (class "Default")
      (node (ref "AC1") (pin "9") (pinfunction "INT2_9") (pintype "input"))
    )
    (net (code "67") (name "unconnected-(AC1-NC-Pad10)") (class "Default")
      (node (ref "AC1") (pin "10") (pinfunction "NC_10") (pintype "no_connect"))
    )
    (net (code "68") (name "unconnected-(AC1-RESERVED_1-Pad3)") (class "Default")
      (node (ref "AC1") (pin "3") (pinfunction "RESERVED_1_3") (pintype "bidirectional"))
    )
    (net (code "69") (name "unconnected-(AC1-RESERVED_2-Pad11)") (class "Default")
      (node (ref "AC1") (pin "11") (pinfunction "RESERVED_2_11") (pintype "bidirectional"))
    )
    (net (code "70") (name "unconnected-(AC1-SDO{slash}ALT_ADDRESS-Pad12)") (class "Default")
      (node (ref "AC1") (pin "12") (pinfunction "SDO/ALT_ADDRESS_12") (pintype "bidirectional"))
    )
    (net (code "71") (name "unconnected-(AC1-VS-Pad6)") (class "Default")
      (node (ref "AC1") (pin "6") (pinfunction "VS_6") (pintype "bidirectional"))
    )
    (net (code "72") (name "unconnected-(AC1-~{CS}-Pad7)") (class "Default")
      (node (ref "AC1") (pin "7") (pinfunction "~{CS}_7") (pintype "input"))
    )
    (net (code "73") (name "unconnected-(D1-NC-Pad3)") (class "Default")
      (node (ref "D1") (pin "3") (pinfunction "NC_3") (pintype "no_connect"))
    )
    (net (code "74") (name "unconnected-(HDR1-Pad4)") (class "Default")
      (node (ref "HDR1") (pin "4") (pinfunction "4_4") (pintype "bidirectional"))
    )
    (net (code "75") (name "unconnected-(S1-NC-Pad3)") (class "Default")
      (node (ref "S1") (pin "3") (pinfunction "NC_3") (pintype "no_connect"))
    )
    (net (code "76") (name "unconnected-(S1-PadMH1)") (class "Default")
      (node (ref "S1") (pin "MH1") (pinfunction "MH1_MH1") (pintype "bidirectional"))
    )
    (net (code "77") (name "unconnected-(S1-PadMH2)") (class "Default")
      (node (ref "S1") (pin "MH2") (pinfunction "MH2_MH2") (pintype "bidirectional"))
    )
    (net (code "78") (name "unconnected-(S1-PadMH3)") (class "Default")
      (node (ref "S1") (pin "MH3") (pinfunction "MH3_MH3") (pintype "bidirectional"))
    )
    (net (code "79") (name "unconnected-(S1-PadMH4)") (class "Default")
      (node (ref "S1") (pin "MH4") (pinfunction "MH4_MH4") (pintype "bidirectional"))
    )
    (net (code "80") (name "unconnected-(U2-ANTSEL1-Pad29)") (class "Default")
      (node (ref "U2") (pin "29") (pinfunction "ANTSEL1_29") (pintype "output"))
    )
    (net (code "81") (name "unconnected-(U2-ANTSEL2-Pad30)") (class "Default")
      (node (ref "U2") (pin "30") (pinfunction "ANTSEL2_30") (pintype "output"))
    )
    (net (code "82") (name "unconnected-(U2-DCDC_ANA2_SW_P-Pad45)") (class "Default")
      (node (ref "U2") (pin "45") (pinfunction "DCDC_ANA2_SW_P_45") (pintype "bidirectional"))
    )
    (net (code "83") (name "unconnected-(U2-GPIO0-Pad50)") (class "Default")
      (node (ref "U2") (pin "50") (pinfunction "GPIO0_50") (pintype "bidirectional"))
    )
    (net (code "84") (name "unconnected-(U2-GPIO1-Pad55)") (class "Default")
      (node (ref "U2") (pin "55") (pinfunction "GPIO1_55") (pintype "bidirectional"))
    )
    (net (code "85") (name "unconnected-(U2-GPIO6-Pad61)") (class "Default")
      (node (ref "U2") (pin "61") (pinfunction "GPIO6_61") (pintype "bidirectional"))
    )
    (net (code "86") (name "unconnected-(U2-GPIO7-Pad62)") (class "Default")
      (node (ref "U2") (pin "62") (pinfunction "GPIO7_62") (pintype "bidirectional"))
    )
    (net (code "87") (name "unconnected-(U2-GPIO8-Pad63)") (class "Default")
      (node (ref "U2") (pin "63") (pinfunction "GPIO8_63") (pintype "bidirectional"))
    )
    (net (code "88") (name "unconnected-(U2-GPIO9-Pad64)") (class "Default")
      (node (ref "U2") (pin "64") (pinfunction "GPIO9_64") (pintype "bidirectional"))
    )
    (net (code "89") (name "unconnected-(U2-GPIO28-Pad18)") (class "Default")
      (node (ref "U2") (pin "18") (pinfunction "GPIO28_18") (pintype "bidirectional"))
    )
    (net (code "90") (name "unconnected-(U2-GPIO30-Pad53)") (class "Default")
      (node (ref "U2") (pin "53") (pinfunction "GPIO30_53") (pintype "bidirectional"))
    )
    (net (code "91") (name "unconnected-(U2-NC-Pad28)") (class "Default")
      (node (ref "U2") (pin "28") (pinfunction "NC_28") (pintype "passive"))
    )
    (net (code "92") (name "unconnected-(U2-NC_2-Pad26)") (class "Default")
      (node (ref "U2") (pin "26") (pinfunction "NC_2_26") (pintype "passive"))
    )
    (net (code "93") (name "unconnected-(U2-NC_3-Pad27)") (class "Default")
      (node (ref "U2") (pin "27") (pinfunction "NC_3_27") (pintype "passive"))
    )
    (net (code "94") (name "unconnected-(U2-RESET_N-Pad32)") (class "Default")
      (node (ref "U2") (pin "32") (pinfunction "RESET_N_32") (pintype "input"))
    )
    (net (code "95") (name "unconnected-(U2-RF_BG-Pad31)") (class "Default")
      (node (ref "U2") (pin "31") (pinfunction "RF_BG_31") (pintype "passive"))
    )
    (net (code "96") (name "unconnected-(U2-WLAN_XTAL_N-Pad22)") (class "Default")
      (node (ref "U2") (pin "22") (pinfunction "WLAN_XTAL_N_22") (pintype "passive"))
    )
    (net (code "97") (name "unconnected-(U2-WLAN_XTAL_P-Pad23)") (class "Default")
      (node (ref "U2") (pin "23") (pinfunction "WLAN_XTAL_P_23") (pintype "passive"))
    )
    (net (code "98") (name "unconnected-(U3-AI_0-PadP10)") (class "Default")
      (node (ref "U3") (pin "P10") (pinfunction "AI_0_P10") (pintype "bidirectional"))
    )
    (net (code "99") (name "unconnected-(U3-AI_1-PadP8)") (class "Default")
      (node (ref "U3") (pin "P8") (pinfunction "AI_1_P8") (pintype "bidirectional"))
    )
    (net (code "100") (name "unconnected-(U3-AI_2-PadP7)") (class "Default")
      (node (ref "U3") (pin "P7") (pinfunction "AI_2_P7") (pintype "bidirectional"))
    )
    (net (code "101") (name "unconnected-(U3-AI_3-PadP9)") (class "Default")
      (node (ref "U3") (pin "P9") (pinfunction "AI_3_P9") (pintype "bidirectional"))
    )
    (net (code "102") (name "unconnected-(U3-GPIO17-PadP4)") (class "Default")
      (node (ref "U3") (pin "P4") (pinfunction "GPIO17_P4") (pintype "bidirectional"))
    )
    (net (code "103") (name "unconnected-(U3-GPIO18-PadP5)") (class "Default")
      (node (ref "U3") (pin "P5") (pinfunction "GPIO18_P5") (pintype "bidirectional"))
    )
    (net (code "104") (name "unconnected-(U3-GPIO19-PadP6)") (class "Default")
      (node (ref "U3") (pin "P6") (pinfunction "GPIO19_P6") (pintype "bidirectional"))
    )
    (net (code "105") (name "unconnected-(U3-GPIO23-PadP21)") (class "Default")
      (node (ref "U3") (pin "P21") (pinfunction "GPIO23_P21") (pintype "bidirectional"))
    )
    (net (code "106") (name "unconnected-(U3-IPCS_SCK-PadP36)") (class "Default")
      (node (ref "U3") (pin "P36") (pinfunction "IPCS_SCK_P36") (pintype "bidirectional"))
    )
    (net (code "107") (name "unconnected-(U3-LPTIMER_EXT-PadP26)") (class "Default")
      (node (ref "U3") (pin "P26") (pinfunction "LPTIMER_EXT_P26") (pintype "bidirectional"))
    )
    (net (code "108") (name "unconnected-(U3-NC1-PadP3)") (class "Default")
      (node (ref "U3") (pin "P3") (pinfunction "NC1_P3") (pintype "bidirectional"))
    )
    (net (code "109") (name "unconnected-(U3-NC2-PadP13)") (class "Default")
      (node (ref "U3") (pin "P13") (pinfunction "NC2_P13") (pintype "bidirectional"))
    )
    (net (code "110") (name "unconnected-(U3-NC3-PadP14)") (class "Default")
      (node (ref "U3") (pin "P14") (pinfunction "NC3_P14") (pintype "bidirectional"))
    )
    (net (code "111") (name "unconnected-(U3-NC4-PadP29)") (class "Default")
      (node (ref "U3") (pin "P29") (pinfunction "NC4_P29") (pintype "bidirectional"))
    )
    (net (code "112") (name "unconnected-(U3-NC5-PadP52)") (class "Default")
      (node (ref "U3") (pin "P52") (pinfunction "NC5_P52") (pintype "bidirectional"))
    )
    (net (code "113") (name "unconnected-(U3-NC6-PadP53)") (class "Default")
      (node (ref "U3") (pin "P53") (pinfunction "NC6_P53") (pintype "bidirectional"))
    )
    (net (code "114") (name "unconnected-(U3-NC7-PadP65)") (class "Default")
      (node (ref "U3") (pin "P65") (pinfunction "NC7_P65") (pintype "bidirectional"))
    )
    (net (code "115") (name "unconnected-(U3-P$2-PadP2)") (class "Default")
      (node (ref "U3") (pin "P2") (pinfunction "P$2_P2") (pintype "bidirectional"))
    )
    (net (code "116") (name "unconnected-(U3-P$12-PadP12)") (class "Default")
      (node (ref "U3") (pin "P12") (pinfunction "P$12_P12") (pintype "bidirectional"))
    )
    (net (code "117") (name "unconnected-(U3-P$22-PadP22)") (class "Default")
      (node (ref "U3") (pin "P22") (pinfunction "P$22_P22") (pintype "bidirectional"))
    )
    (net (code "118") (name "unconnected-(U3-P$23-PadP23)") (class "Default")
      (node (ref "U3") (pin "P23") (pinfunction "P$23_P23") (pintype "bidirectional"))
    )
    (net (code "119") (name "unconnected-(U3-P$24-PadP24)") (class "Default")
      (node (ref "U3") (pin "P24") (pinfunction "P$24_P24") (pintype "bidirectional"))
    )
    (net (code "120") (name "unconnected-(U3-P$54-PadP54)") (class "Default")
      (node (ref "U3") (pin "P54") (pinfunction "P$54_P54") (pintype "bidirectional"))
    )
    (net (code "121") (name "unconnected-(U3-PWM0{slash}TIMER16_OUT-PadP46)") (class "Default")
      (node (ref "U3") (pin "P46") (pinfunction "PWM0/TIMER16_OUT_P46") (pintype "bidirectional"))
    )
    (net (code "122") (name "unconnected-(U3-RADIO_INHIBIT-PadP64)") (class "Default")
      (node (ref "U3") (pin "P64") (pinfunction "RADIO_INHIBIT_P64") (pintype "bidirectional"))
    )
    (net (code "123") (name "unconnected-(U3-SLEEPN-PadP27)") (class "Default")
      (node (ref "U3") (pin "P27") (pinfunction "SLEEPN_P27") (pintype "bidirectional"))
    )
    (net (code "124") (name "unconnected-(U3-SPIM_MISO-PadP38)") (class "Default")
      (node (ref "U3") (pin "P38") (pinfunction "SPIM_MISO_P38") (pintype "bidirectional"))
    )
    (net (code "125") (name "unconnected-(U3-SPIM_MOSI-PadP40)") (class "Default")
      (node (ref "U3") (pin "P40") (pinfunction "SPIM_MOSI_P40") (pintype "bidirectional"))
    )
    (net (code "126") (name "unconnected-(U3-SPIM_SCK-PadP41)") (class "Default")
      (node (ref "U3") (pin "P41") (pinfunction "SPIM_SCK_P41") (pintype "bidirectional"))
    )
    (net (code "127") (name "unconnected-(U3-SPIM_SS_0N-PadP44)") (class "Default")
      (node (ref "U3") (pin "P44") (pinfunction "SPIM_SS_0N_P44") (pintype "bidirectional"))
    )
    (net (code "128") (name "unconnected-(U3-SPIM_SS_1N-PadP43)") (class "Default")
      (node (ref "U3") (pin "P43") (pinfunction "SPIM_SS_1N_P43") (pintype "bidirectional"))
    )
    (net (code "129") (name "unconnected-(U3-SPIM_SS_2N-PadP28)") (class "Default")
      (node (ref "U3") (pin "P28") (pinfunction "SPIM_SS_2N_P28") (pintype "bidirectional"))
    )
    (net (code "130") (name "unconnected-(U3-SPIS_MISO{slash}UARTC1_TX-PadP47)") (class "Default")
      (node (ref "U3") (pin "P47") (pinfunction "SPIS_MISO/UARTC1_TX_P47") (pintype "bidirectional"))
    )
    (net (code "131") (name "unconnected-(U3-SPIS_MOSI_UARTC1_RX-PadP48)") (class "Default")
      (node (ref "U3") (pin "P48") (pinfunction "SPIS_MOSI_UARTC1_RX_P48") (pintype "bidirectional"))
    )
    (net (code "132") (name "unconnected-(U3-SPIS_SSN{slash}SDA-PadP50)") (class "Default")
      (node (ref "U3") (pin "P50") (pinfunction "SPIS_SSN/SDA_P50") (pintype "bidirectional"))
    )
    (net (code "133") (name "unconnected-(U3-TCK-PadP19)") (class "Default")
      (node (ref "U3") (pin "P19") (pinfunction "TCK_P19") (pintype "bidirectional"))
    )
    (net (code "134") (name "unconnected-(U3-TDI-PadP16)") (class "Default")
      (node (ref "U3") (pin "P16") (pinfunction "TDI_P16") (pintype "bidirectional"))
    )
    (net (code "135") (name "unconnected-(U3-TDO-PadP17)") (class "Default")
      (node (ref "U3") (pin "P17") (pinfunction "TDO_P17") (pintype "bidirectional"))
    )
    (net (code "136") (name "unconnected-(U3-TIMEN-PadP63)") (class "Default")
      (node (ref "U3") (pin "P63") (pinfunction "TIMEN_P63") (pintype "bidirectional"))
    )
    (net (code "137") (name "unconnected-(U3-TIMER8_EXT-PadP25)") (class "Default")
      (node (ref "U3") (pin "P25") (pinfunction "TIMER8_EXT_P25") (pintype "bidirectional"))
    )
    (net (code "138") (name "unconnected-(U3-TIMER16_EXT-PadP45)") (class "Default")
      (node (ref "U3") (pin "P45") (pinfunction "TIMER16_EXT_P45") (pintype "bidirectional"))
    )
    (net (code "139") (name "unconnected-(U3-TMS-PadP18)") (class "Default")
      (node (ref "U3") (pin "P18") (pinfunction "TMS_P18") (pintype "bidirectional"))
    )
    (net (code "140") (name "unconnected-(U3-UART_RX-PadP59)") (class "Default")
      (node (ref "U3") (pin "P59") (pinfunction "UART_RX_P59") (pintype "bidirectional"))
    )
    (net (code "141") (name "unconnected-(U3-UART_RX_CTSN-PadP58)") (class "Default")
      (node (ref "U3") (pin "P58") (pinfunction "UART_RX_CTSN_P58") (pintype "bidirectional"))
    )
    (net (code "142") (name "unconnected-(U3-UART_RX_RTSN-PadP57)") (class "Default")
      (node (ref "U3") (pin "P57") (pinfunction "UART_RX_RTSN_P57") (pintype "bidirectional"))
    )
    (net (code "143") (name "unconnected-(U3-UART_TX-PadP62)") (class "Default")
      (node (ref "U3") (pin "P62") (pinfunction "UART_TX_P62") (pintype "bidirectional"))
    )
    (net (code "144") (name "unconnected-(U3-UART_TX_CTSN-PadP61)") (class "Default")
      (node (ref "U3") (pin "P61") (pinfunction "UART_TX_CTSN_P61") (pintype "bidirectional"))
    )
    (net (code "145") (name "unconnected-(U3-UART_TX_RTSN-PadP60)") (class "Default")
      (node (ref "U3") (pin "P60") (pinfunction "UART_TX_RTSN_P60") (pintype "bidirectional"))
    )
  )
)
